# SamBreakOutSmall.net
KiCad netlist of a schematic drawn in EAGLE
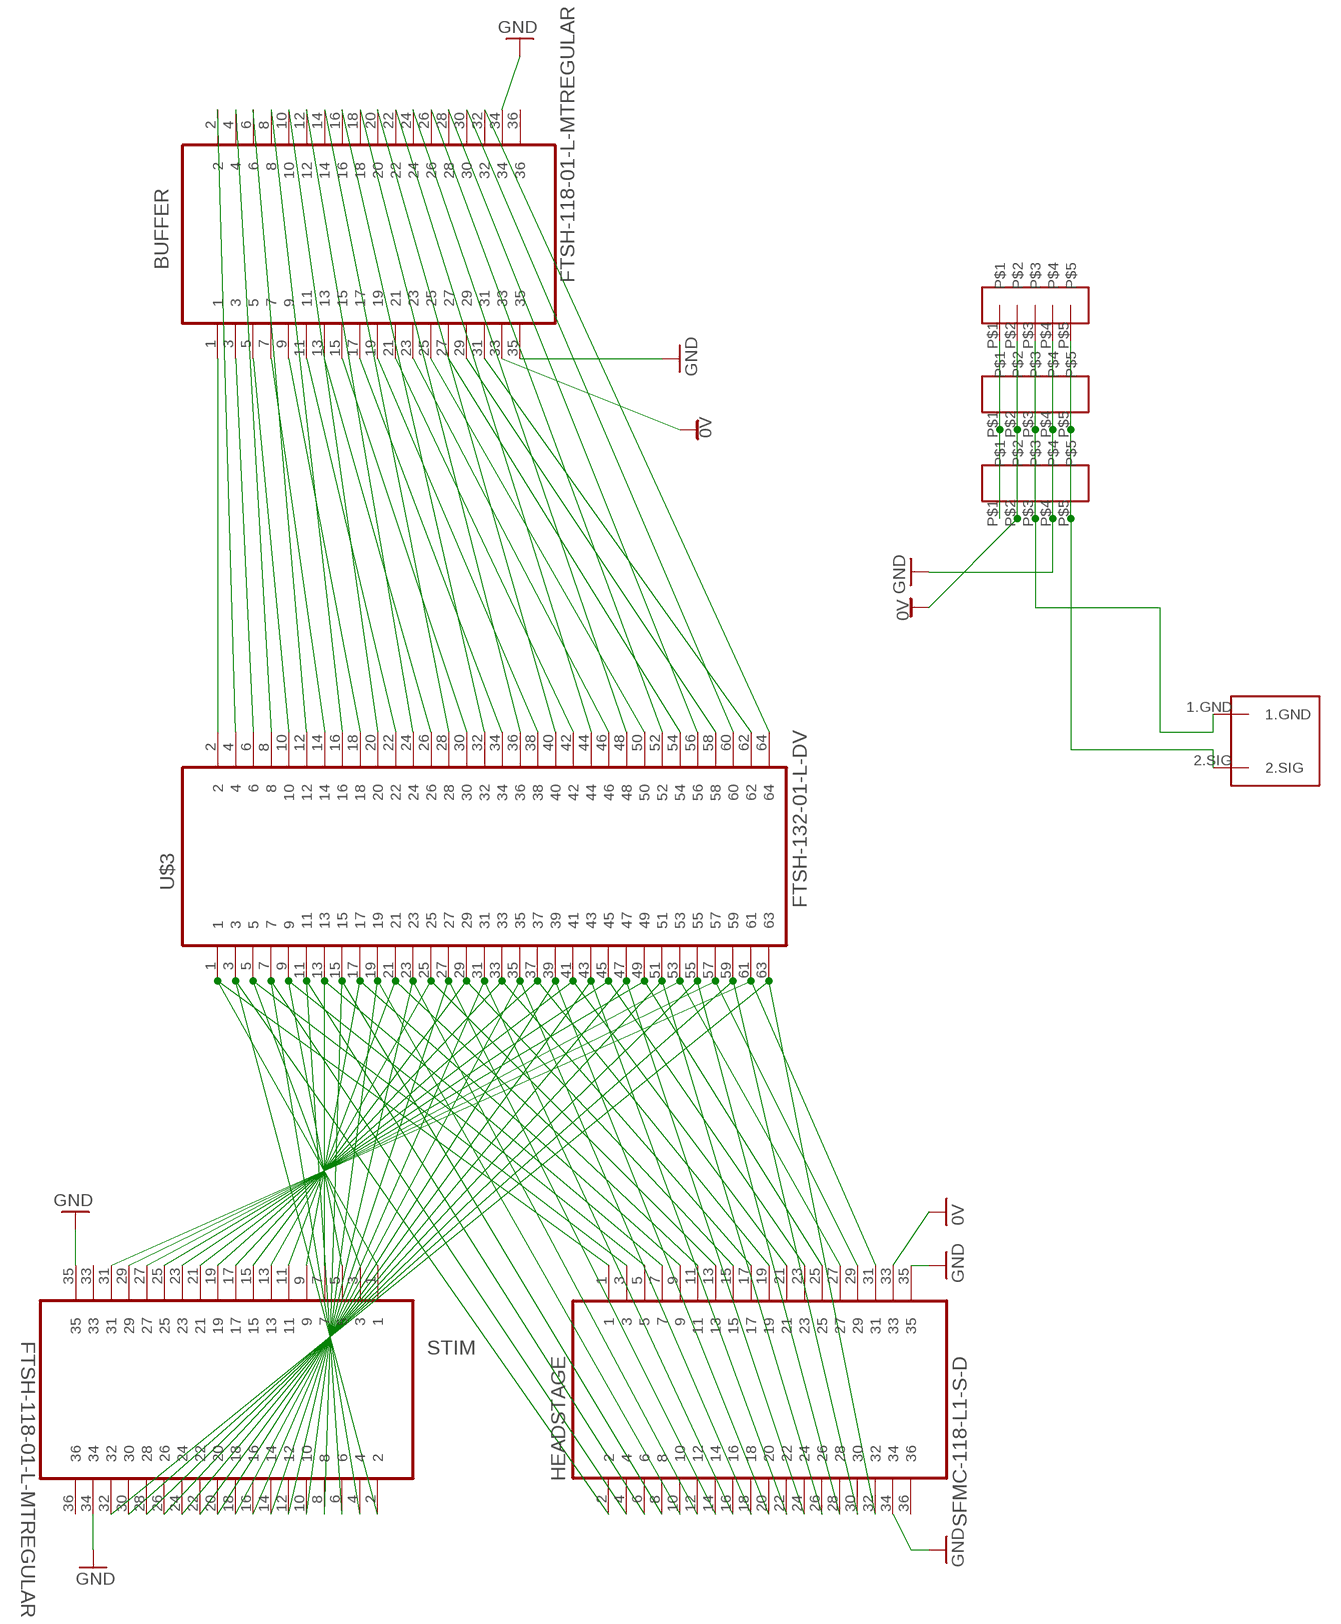
[diagram p0: schematic, sheet 1]

(export (version "E")
  (design (tool "Eeschema 10.0.6"))
  (components
    (comp (ref "BUFFER")
      (value "FTSH-118-01-L-MTREGULAR")
      (footprint "eagle-import:FTSH-118-01-L-MT")
      (libsource (lib "eagle-import") (part "FTSH-118-01-L-MTREGULAR"))
    )
    (comp (ref "HEADSTAGE")
      (value "SFMC-118-L1-S-D")
      (footprint "eagle-import:SFMC-118-L1-S-D")
      (libsource (lib "eagle-import") (part "SFMC-118-L1-S-D"))
    )
    (comp (ref "STIM")
      (value "FTSH-118-01-L-MTREGULAR")
      (footprint "eagle-import:FTSH-118-01-L-MT")
      (libsource (lib "eagle-import") (part "FTSH-118-01-L-MTREGULAR"))
    )
    (comp (ref "U$1")
      (value "BNCRAMOUNT")
      (footprint "eagle-import:BNCRAMOUNT")
      (libsource (lib "eagle-import") (part "BNCRAMOUNT"))
    )
    (comp (ref "U$3")
      (value "FTSH-132-01-L-DV")
      (footprint "eagle-import:FTSH-132-01-DV")
      (libsource (lib "eagle-import") (part "FTSH-132-01-L-DV"))
    )
    (comp (ref "U$34")
      (value "LPPB051NFFN-RC")
      (footprint "eagle-import:LPPB051NFFN-RC")
      (libsource (lib "eagle-import") (part "LPPB051NFFN-RC"))
    )
    (comp (ref "U$35")
      (value "LPPB051NFFN-RC")
      (footprint "eagle-import:LPPB051NFFN-RC")
      (libsource (lib "eagle-import") (part "LPPB051NFFN-RC"))
    )
    (comp (ref "U$36")
      (value "LPPB051NFFN-RC")
      (footprint "eagle-import:LPPB051NFFN-RC")
      (libsource (lib "eagle-import") (part "LPPB051NFFN-RC"))
    )
  )
  (nets
    (net (code "1") (name "0V") (class "Default")
      (node (ref "BUFFER") (pin "33") (pinfunction "33_33") (pintype "passive"))
      (node (ref "HEADSTAGE") (pin "33") (pinfunction "33_33") (pintype "passive"))
      (node (ref "U$34") (pin "P$2") (pinfunction "P$2_P$2") (pintype "bidirectional"))
      (node (ref "U$35") (pin "P$2") (pinfunction "P$2_P$2") (pintype "bidirectional"))
      (node (ref "U$36") (pin "P$2") (pinfunction "P$2_P$2") (pintype "bidirectional"))
    )
    (net (code "2") (name "GND") (class "Default")
      (node (ref "BUFFER") (pin "34") (pinfunction "34_34") (pintype "passive"))
      (node (ref "BUFFER") (pin "35") (pinfunction "35_35") (pintype "passive"))
      (node (ref "HEADSTAGE") (pin "34") (pinfunction "34_34") (pintype "passive"))
      (node (ref "HEADSTAGE") (pin "35") (pinfunction "35_35") (pintype "passive"))
      (node (ref "STIM") (pin "34") (pinfunction "34_34") (pintype "passive"))
      (node (ref "STIM") (pin "35") (pinfunction "35_35") (pintype "passive"))
      (node (ref "U$34") (pin "P$4") (pinfunction "P$4_P$4") (pintype "bidirectional"))
      (node (ref "U$35") (pin "P$4") (pinfunction "P$4_P$4") (pintype "bidirectional"))
      (node (ref "U$36") (pin "P$4") (pinfunction "P$4_P$4") (pintype "bidirectional"))
    )
    (net (code "3") (name "Net-(BUFFER-Pad1)") (class "Default")
      (node (ref "BUFFER") (pin "1") (pinfunction "1_1") (pintype "passive"))
      (node (ref "U$3") (pin "2") (pinfunction "2_2") (pintype "passive"))
    )
    (net (code "4") (name "Net-(BUFFER-Pad2)") (class "Default")
      (node (ref "BUFFER") (pin "2") (pinfunction "2_2") (pintype "passive"))
      (node (ref "U$3") (pin "4") (pinfunction "4_4") (pintype "passive"))
    )
    (net (code "5") (name "Net-(BUFFER-Pad3)") (class "Default")
      (node (ref "BUFFER") (pin "3") (pinfunction "3_3") (pintype "passive"))
      (node (ref "U$3") (pin "6") (pinfunction "6_6") (pintype "passive"))
    )
    (net (code "6") (name "Net-(BUFFER-Pad4)") (class "Default")
      (node (ref "BUFFER") (pin "4") (pinfunction "4_4") (pintype "passive"))
      (node (ref "U$3") (pin "8") (pinfunction "8_8") (pintype "passive"))
    )
    (net (code "7") (name "Net-(BUFFER-Pad5)") (class "Default")
      (node (ref "BUFFER") (pin "5") (pinfunction "5_5") (pintype "passive"))
      (node (ref "U$3") (pin "10") (pinfunction "10_10") (pintype "passive"))
    )
    (net (code "8") (name "Net-(BUFFER-Pad6)") (class "Default")
      (node (ref "BUFFER") (pin "6") (pinfunction "6_6") (pintype "passive"))
      (node (ref "U$3") (pin "12") (pinfunction "12_12") (pintype "passive"))
    )
    (net (code "9") (name "Net-(BUFFER-Pad7)") (class "Default")
      (node (ref "BUFFER") (pin "7") (pinfunction "7_7") (pintype "passive"))
      (node (ref "U$3") (pin "14") (pinfunction "14_14") (pintype "passive"))
    )
    (net (code "10") (name "Net-(BUFFER-Pad8)") (class "Default")
      (node (ref "BUFFER") (pin "8") (pinfunction "8_8") (pintype "passive"))
      (node (ref "U$3") (pin "16") (pinfunction "16_16") (pintype "passive"))
    )
    (net (code "11") (name "Net-(BUFFER-Pad9)") (class "Default")
      (node (ref "BUFFER") (pin "9") (pinfunction "9_9") (pintype "passive"))
      (node (ref "U$3") (pin "18") (pinfunction "18_18") (pintype "passive"))
    )
    (net (code "12") (name "Net-(BUFFER-Pad10)") (class "Default")
      (node (ref "BUFFER") (pin "10") (pinfunction "10_10") (pintype "passive"))
      (node (ref "U$3") (pin "20") (pinfunction "20_20") (pintype "passive"))
    )
    (net (code "13") (name "Net-(BUFFER-Pad11)") (class "Default")
      (node (ref "BUFFER") (pin "11") (pinfunction "11_11") (pintype "passive"))
      (node (ref "U$3") (pin "22") (pinfunction "22_22") (pintype "passive"))
    )
    (net (code "14") (name "Net-(BUFFER-Pad12)") (class "Default")
      (node (ref "BUFFER") (pin "12") (pinfunction "12_12") (pintype "passive"))
      (node (ref "U$3") (pin "24") (pinfunction "24_24") (pintype "passive"))
    )
    (net (code "15") (name "Net-(BUFFER-Pad13)") (class "Default")
      (node (ref "BUFFER") (pin "13") (pinfunction "13_13") (pintype "passive"))
      (node (ref "U$3") (pin "26") (pinfunction "26_26") (pintype "passive"))
    )
    (net (code "16") (name "Net-(BUFFER-Pad14)") (class "Default")
      (node (ref "BUFFER") (pin "14") (pinfunction "14_14") (pintype "passive"))
      (node (ref "U$3") (pin "28") (pinfunction "28_28") (pintype "passive"))
    )
    (net (code "17") (name "Net-(BUFFER-Pad15)") (class "Default")
      (node (ref "BUFFER") (pin "15") (pinfunction "15_15") (pintype "passive"))
      (node (ref "U$3") (pin "30") (pinfunction "30_30") (pintype "passive"))
    )
    (net (code "18") (name "Net-(BUFFER-Pad16)") (class "Default")
      (node (ref "BUFFER") (pin "16") (pinfunction "16_16") (pintype "passive"))
      (node (ref "U$3") (pin "32") (pinfunction "32_32") (pintype "passive"))
    )
    (net (code "19") (name "Net-(BUFFER-Pad17)") (class "Default")
      (node (ref "BUFFER") (pin "17") (pinfunction "17_17") (pintype "passive"))
      (node (ref "U$3") (pin "34") (pinfunction "34_34") (pintype "passive"))
    )
    (net (code "20") (name "Net-(BUFFER-Pad18)") (class "Default")
      (node (ref "BUFFER") (pin "18") (pinfunction "18_18") (pintype "passive"))
      (node (ref "U$3") (pin "36") (pinfunction "36_36") (pintype "passive"))
    )
    (net (code "21") (name "Net-(BUFFER-Pad19)") (class "Default")
      (node (ref "BUFFER") (pin "19") (pinfunction "19_19") (pintype "passive"))
      (node (ref "U$3") (pin "38") (pinfunction "38_38") (pintype "bidirectional"))
    )
    (net (code "22") (name "Net-(BUFFER-Pad20)") (class "Default")
      (node (ref "BUFFER") (pin "20") (pinfunction "20_20") (pintype "passive"))
      (node (ref "U$3") (pin "40") (pinfunction "40_40") (pintype "bidirectional"))
    )
    (net (code "23") (name "Net-(BUFFER-Pad21)") (class "Default")
      (node (ref "BUFFER") (pin "21") (pinfunction "21_21") (pintype "passive"))
      (node (ref "U$3") (pin "42") (pinfunction "42_42") (pintype "bidirectional"))
    )
    (net (code "24") (name "Net-(BUFFER-Pad22)") (class "Default")
      (node (ref "BUFFER") (pin "22") (pinfunction "22_22") (pintype "passive"))
      (node (ref "U$3") (pin "44") (pinfunction "44_44") (pintype "bidirectional"))
    )
    (net (code "25") (name "Net-(BUFFER-Pad23)") (class "Default")
      (node (ref "BUFFER") (pin "23") (pinfunction "23_23") (pintype "passive"))
      (node (ref "U$3") (pin "46") (pinfunction "46_46") (pintype "bidirectional"))
    )
    (net (code "26") (name "Net-(BUFFER-Pad24)") (class "Default")
      (node (ref "BUFFER") (pin "24") (pinfunction "24_24") (pintype "passive"))
      (node (ref "U$3") (pin "48") (pinfunction "48_48") (pintype "bidirectional"))
    )
    (net (code "27") (name "Net-(BUFFER-Pad25)") (class "Default")
      (node (ref "BUFFER") (pin "25") (pinfunction "25_25") (pintype "passive"))
      (node (ref "U$3") (pin "50") (pinfunction "50_50") (pintype "bidirectional"))
    )
    (net (code "28") (name "Net-(BUFFER-Pad26)") (class "Default")
      (node (ref "BUFFER") (pin "26") (pinfunction "26_26") (pintype "passive"))
      (node (ref "U$3") (pin "52") (pinfunction "52_52") (pintype "bidirectional"))
    )
    (net (code "29") (name "Net-(BUFFER-Pad27)") (class "Default")
      (node (ref "BUFFER") (pin "27") (pinfunction "27_27") (pintype "passive"))
      (node (ref "U$3") (pin "54") (pinfunction "54_54") (pintype "bidirectional"))
    )
    (net (code "30") (name "Net-(BUFFER-Pad28)") (class "Default")
      (node (ref "BUFFER") (pin "28") (pinfunction "28_28") (pintype "passive"))
      (node (ref "U$3") (pin "56") (pinfunction "56_56") (pintype "bidirectional"))
    )
    (net (code "31") (name "Net-(BUFFER-Pad29)") (class "Default")
      (node (ref "BUFFER") (pin "29") (pinfunction "29_29") (pintype "passive"))
      (node (ref "U$3") (pin "58") (pinfunction "58_58") (pintype "bidirectional"))
    )
    (net (code "32") (name "Net-(BUFFER-Pad30)") (class "Default")
      (node (ref "BUFFER") (pin "30") (pinfunction "30_30") (pintype "passive"))
      (node (ref "U$3") (pin "60") (pinfunction "60_60") (pintype "bidirectional"))
    )
    (net (code "33") (name "Net-(BUFFER-Pad31)") (class "Default")
      (node (ref "BUFFER") (pin "31") (pinfunction "31_31") (pintype "passive"))
      (node (ref "U$3") (pin "62") (pinfunction "62_62") (pintype "bidirectional"))
    )
    (net (code "34") (name "Net-(BUFFER-Pad32)") (class "Default")
      (node (ref "BUFFER") (pin "32") (pinfunction "32_32") (pintype "passive"))
      (node (ref "U$3") (pin "64") (pinfunction "64_64") (pintype "bidirectional"))
    )
    (net (code "35") (name "Net-(HEADSTAGE-Pad1)") (class "Default")
      (node (ref "HEADSTAGE") (pin "1") (pinfunction "1_1") (pintype "passive"))
      (node (ref "STIM") (pin "1") (pinfunction "1_1") (pintype "passive"))
      (node (ref "U$3") (pin "1") (pinfunction "1_1") (pintype "passive"))
    )
    (net (code "36") (name "Net-(HEADSTAGE-Pad2)") (class "Default")
      (node (ref "HEADSTAGE") (pin "2") (pinfunction "2_2") (pintype "passive"))
      (node (ref "STIM") (pin "2") (pinfunction "2_2") (pintype "passive"))
      (node (ref "U$3") (pin "3") (pinfunction "3_3") (pintype "passive"))
    )
    (net (code "37") (name "Net-(HEADSTAGE-Pad3)") (class "Default")
      (node (ref "HEADSTAGE") (pin "3") (pinfunction "3_3") (pintype "passive"))
      (node (ref "STIM") (pin "3") (pinfunction "3_3") (pintype "passive"))
      (node (ref "U$3") (pin "5") (pinfunction "5_5") (pintype "passive"))
    )
    (net (code "38") (name "Net-(HEADSTAGE-Pad4)") (class "Default")
      (node (ref "HEADSTAGE") (pin "4") (pinfunction "4_4") (pintype "passive"))
      (node (ref "STIM") (pin "4") (pinfunction "4_4") (pintype "passive"))
      (node (ref "U$3") (pin "7") (pinfunction "7_7") (pintype "passive"))
    )
    (net (code "39") (name "Net-(HEADSTAGE-Pad5)") (class "Default")
      (node (ref "HEADSTAGE") (pin "5") (pinfunction "5_5") (pintype "passive"))
      (node (ref "STIM") (pin "5") (pinfunction "5_5") (pintype "passive"))
      (node (ref "U$3") (pin "9") (pinfunction "9_9") (pintype "passive"))
    )
    (net (code "40") (name "Net-(HEADSTAGE-Pad6)") (class "Default")
      (node (ref "HEADSTAGE") (pin "6") (pinfunction "6_6") (pintype "passive"))
      (node (ref "STIM") (pin "6") (pinfunction "6_6") (pintype "passive"))
      (node (ref "U$3") (pin "11") (pinfunction "11_11") (pintype "passive"))
    )
    (net (code "41") (name "Net-(HEADSTAGE-Pad7)") (class "Default")
      (node (ref "HEADSTAGE") (pin "7") (pinfunction "7_7") (pintype "passive"))
      (node (ref "STIM") (pin "7") (pinfunction "7_7") (pintype "passive"))
      (node (ref "U$3") (pin "13") (pinfunction "13_13") (pintype "passive"))
    )
    (net (code "42") (name "Net-(HEADSTAGE-Pad8)") (class "Default")
      (node (ref "HEADSTAGE") (pin "8") (pinfunction "8_8") (pintype "passive"))
      (node (ref "STIM") (pin "8") (pinfunction "8_8") (pintype "passive"))
      (node (ref "U$3") (pin "15") (pinfunction "15_15") (pintype "passive"))
    )
    (net (code "43") (name "Net-(HEADSTAGE-Pad9)") (class "Default")
      (node (ref "HEADSTAGE") (pin "9") (pinfunction "9_9") (pintype "passive"))
      (node (ref "STIM") (pin "9") (pinfunction "9_9") (pintype "passive"))
      (node (ref "U$3") (pin "17") (pinfunction "17_17") (pintype "passive"))
    )
    (net (code "44") (name "Net-(HEADSTAGE-Pad10)") (class "Default")
      (node (ref "HEADSTAGE") (pin "10") (pinfunction "10_10") (pintype "passive"))
      (node (ref "STIM") (pin "10") (pinfunction "10_10") (pintype "passive"))
      (node (ref "U$3") (pin "19") (pinfunction "19_19") (pintype "passive"))
    )
    (net (code "45") (name "Net-(HEADSTAGE-Pad11)") (class "Default")
      (node (ref "HEADSTAGE") (pin "11") (pinfunction "11_11") (pintype "passive"))
      (node (ref "STIM") (pin "11") (pinfunction "11_11") (pintype "passive"))
      (node (ref "U$3") (pin "21") (pinfunction "21_21") (pintype "passive"))
    )
    (net (code "46") (name "Net-(HEADSTAGE-Pad12)") (class "Default")
      (node (ref "HEADSTAGE") (pin "12") (pinfunction "12_12") (pintype "passive"))
      (node (ref "STIM") (pin "12") (pinfunction "12_12") (pintype "passive"))
      (node (ref "U$3") (pin "23") (pinfunction "23_23") (pintype "passive"))
    )
    (net (code "47") (name "Net-(HEADSTAGE-Pad13)") (class "Default")
      (node (ref "HEADSTAGE") (pin "13") (pinfunction "13_13") (pintype "passive"))
      (node (ref "STIM") (pin "13") (pinfunction "13_13") (pintype "passive"))
      (node (ref "U$3") (pin "25") (pinfunction "25_25") (pintype "passive"))
    )
    (net (code "48") (name "Net-(HEADSTAGE-Pad14)") (class "Default")
      (node (ref "HEADSTAGE") (pin "14") (pinfunction "14_14") (pintype "passive"))
      (node (ref "STIM") (pin "14") (pinfunction "14_14") (pintype "passive"))
      (node (ref "U$3") (pin "27") (pinfunction "27_27") (pintype "passive"))
    )
    (net (code "49") (name "Net-(HEADSTAGE-Pad15)") (class "Default")
      (node (ref "HEADSTAGE") (pin "15") (pinfunction "15_15") (pintype "passive"))
      (node (ref "STIM") (pin "15") (pinfunction "15_15") (pintype "passive"))
      (node (ref "U$3") (pin "29") (pinfunction "29_29") (pintype "passive"))
    )
    (net (code "50") (name "Net-(HEADSTAGE-Pad16)") (class "Default")
      (node (ref "HEADSTAGE") (pin "16") (pinfunction "16_16") (pintype "passive"))
      (node (ref "STIM") (pin "16") (pinfunction "16_16") (pintype "passive"))
      (node (ref "U$3") (pin "31") (pinfunction "31_31") (pintype "passive"))
    )
    (net (code "51") (name "Net-(HEADSTAGE-Pad17)") (class "Default")
      (node (ref "HEADSTAGE") (pin "17") (pinfunction "17_17") (pintype "passive"))
      (node (ref "STIM") (pin "17") (pinfunction "17_17") (pintype "passive"))
      (node (ref "U$3") (pin "33") (pinfunction "33_33") (pintype "passive"))
    )
    (net (code "52") (name "Net-(HEADSTAGE-Pad18)") (class "Default")
      (node (ref "HEADSTAGE") (pin "18") (pinfunction "18_18") (pintype "passive"))
      (node (ref "STIM") (pin "18") (pinfunction "18_18") (pintype "passive"))
      (node (ref "U$3") (pin "35") (pinfunction "35_35") (pintype "passive"))
    )
    (net (code "53") (name "Net-(HEADSTAGE-Pad19)") (class "Default")
      (node (ref "HEADSTAGE") (pin "19") (pinfunction "19_19") (pintype "passive"))
      (node (ref "STIM") (pin "19") (pinfunction "19_19") (pintype "passive"))
      (node (ref "U$3") (pin "37") (pinfunction "37_37") (pintype "bidirectional"))
    )
    (net (code "54") (name "Net-(HEADSTAGE-Pad20)") (class "Default")
      (node (ref "HEADSTAGE") (pin "20") (pinfunction "20_20") (pintype "passive"))
      (node (ref "STIM") (pin "20") (pinfunction "20_20") (pintype "passive"))
      (node (ref "U$3") (pin "39") (pinfunction "39_39") (pintype "bidirectional"))
    )
    (net (code "55") (name "Net-(HEADSTAGE-Pad21)") (class "Default")
      (node (ref "HEADSTAGE") (pin "21") (pinfunction "21_21") (pintype "passive"))
      (node (ref "STIM") (pin "21") (pinfunction "21_21") (pintype "passive"))
      (node (ref "U$3") (pin "41") (pinfunction "41_41") (pintype "bidirectional"))
    )
    (net (code "56") (name "Net-(HEADSTAGE-Pad22)") (class "Default")
      (node (ref "HEADSTAGE") (pin "22") (pinfunction "22_22") (pintype "passive"))
      (node (ref "STIM") (pin "22") (pinfunction "22_22") (pintype "passive"))
      (node (ref "U$3") (pin "43") (pinfunction "43_43") (pintype "bidirectional"))
    )
    (net (code "57") (name "Net-(HEADSTAGE-Pad23)") (class "Default")
      (node (ref "HEADSTAGE") (pin "23") (pinfunction "23_23") (pintype "passive"))
      (node (ref "STIM") (pin "23") (pinfunction "23_23") (pintype "passive"))
      (node (ref "U$3") (pin "45") (pinfunction "45_45") (pintype "bidirectional"))
    )
    (net (code "58") (name "Net-(HEADSTAGE-Pad24)") (class "Default")
      (node (ref "HEADSTAGE") (pin "24") (pinfunction "24_24") (pintype "passive"))
      (node (ref "STIM") (pin "24") (pinfunction "24_24") (pintype "passive"))
      (node (ref "U$3") (pin "47") (pinfunction "47_47") (pintype "bidirectional"))
    )
    (net (code "59") (name "Net-(HEADSTAGE-Pad25)") (class "Default")
      (node (ref "HEADSTAGE") (pin "25") (pinfunction "25_25") (pintype "passive"))
      (node (ref "STIM") (pin "25") (pinfunction "25_25") (pintype "passive"))
      (node (ref "U$3") (pin "49") (pinfunction "49_49") (pintype "bidirectional"))
    )
    (net (code "60") (name "Net-(HEADSTAGE-Pad26)") (class "Default")
      (node (ref "HEADSTAGE") (pin "26") (pinfunction "26_26") (pintype "passive"))
      (node (ref "STIM") (pin "26") (pinfunction "26_26") (pintype "passive"))
      (node (ref "U$3") (pin "51") (pinfunction "51_51") (pintype "bidirectional"))
    )
    (net (code "61") (name "Net-(HEADSTAGE-Pad27)") (class "Default")
      (node (ref "HEADSTAGE") (pin "27") (pinfunction "27_27") (pintype "passive"))
      (node (ref "STIM") (pin "27") (pinfunction "27_27") (pintype "passive"))
      (node (ref "U$3") (pin "53") (pinfunction "53_53") (pintype "bidirectional"))
    )
    (net (code "62") (name "Net-(HEADSTAGE-Pad28)") (class "Default")
      (node (ref "HEADSTAGE") (pin "28") (pinfunction "28_28") (pintype "passive"))
      (node (ref "STIM") (pin "28") (pinfunction "28_28") (pintype "passive"))
      (node (ref "U$3") (pin "55") (pinfunction "55_55") (pintype "bidirectional"))
    )
    (net (code "63") (name "Net-(HEADSTAGE-Pad29)") (class "Default")
      (node (ref "HEADSTAGE") (pin "29") (pinfunction "29_29") (pintype "passive"))
      (node (ref "STIM") (pin "29") (pinfunction "29_29") (pintype "passive"))
      (node (ref "U$3") (pin "57") (pinfunction "57_57") (pintype "bidirectional"))
    )
    (net (code "64") (name "Net-(HEADSTAGE-Pad30)") (class "Default")
      (node (ref "HEADSTAGE") (pin "30") (pinfunction "30_30") (pintype "passive"))
      (node (ref "STIM") (pin "30") (pinfunction "30_30") (pintype "passive"))
      (node (ref "U$3") (pin "59") (pinfunction "59_59") (pintype "bidirectional"))
    )
    (net (code "65") (name "Net-(HEADSTAGE-Pad31)") (class "Default")
      (node (ref "HEADSTAGE") (pin "31") (pinfunction "31_31") (pintype "passive"))
      (node (ref "STIM") (pin "31") (pinfunction "31_31") (pintype "passive"))
      (node (ref "U$3") (pin "61") (pinfunction "61_61") (pintype "bidirectional"))
    )
    (net (code "66") (name "Net-(HEADSTAGE-Pad32)") (class "Default")
      (node (ref "HEADSTAGE") (pin "32") (pinfunction "32_32") (pintype "passive"))
      (node (ref "STIM") (pin "32") (pinfunction "32_32") (pintype "passive"))
      (node (ref "U$3") (pin "63") (pinfunction "63_63") (pintype "bidirectional"))
    )
    (net (code "67") (name "Net-(U$1-Pad1.GND)") (class "Default")
      (node (ref "U$1") (pin "1.GND") (pinfunction "1.GND_1.GND") (pintype "bidirectional"))
      (node (ref "U$34") (pin "P$3") (pinfunction "P$3_P$3") (pintype "bidirectional"))
      (node (ref "U$35") (pin "P$3") (pinfunction "P$3_P$3") (pintype "bidirectional"))
      (node (ref "U$36") (pin "P$3") (pinfunction "P$3_P$3") (pintype "bidirectional"))
    )
    (net (code "68") (name "Net-(U$1-Pad2.SIG)") (class "Default")
      (node (ref "U$1") (pin "2.SIG") (pinfunction "2.SIG_2.SIG") (pintype "bidirectional"))
      (node (ref "U$34") (pin "P$5") (pinfunction "P$5_P$5") (pintype "bidirectional"))
      (node (ref "U$35") (pin "P$5") (pinfunction "P$5_P$5") (pintype "bidirectional"))
      (node (ref "U$36") (pin "P$5") (pinfunction "P$5_P$5") (pintype "bidirectional"))
    )
    (net (code "69") (name "Net-(U$34-PadP$1)") (class "Default")
      (node (ref "U$34") (pin "P$1") (pinfunction "P$1_P$1") (pintype "bidirectional"))
      (node (ref "U$35") (pin "P$1") (pinfunction "P$1_P$1") (pintype "bidirectional"))
      (node (ref "U$36") (pin "P$1") (pinfunction "P$1_P$1") (pintype "bidirectional"))
    )
    (net (code "70") (name "unconnected-(BUFFER-Pad36)") (class "Default")
      (node (ref "BUFFER") (pin "36") (pinfunction "36_36") (pintype "passive"))
    )
    (net (code "71") (name "unconnected-(HEADSTAGE-Pad36)") (class "Default")
      (node (ref "HEADSTAGE") (pin "36") (pinfunction "36_36") (pintype "passive"))
    )
    (net (code "72") (name "unconnected-(STIM-Pad33)") (class "Default")
      (node (ref "STIM") (pin "33") (pinfunction "33_33") (pintype "passive"))
    )
    (net (code "73") (name "unconnected-(STIM-Pad36)") (class "Default")
      (node (ref "STIM") (pin "36") (pinfunction "36_36") (pintype "passive"))
    )
  )
)
